# v7-flex2811_16x.net
KiCad netlist of a schematic drawn in EAGLE
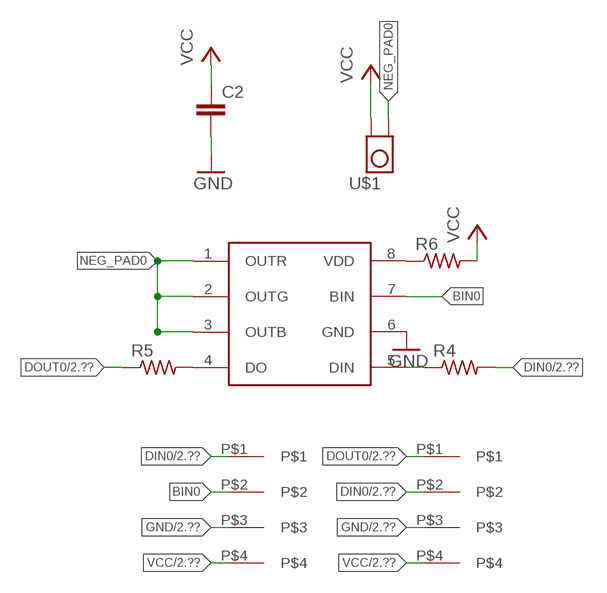
[diagram p0: schematic, sheet 1]
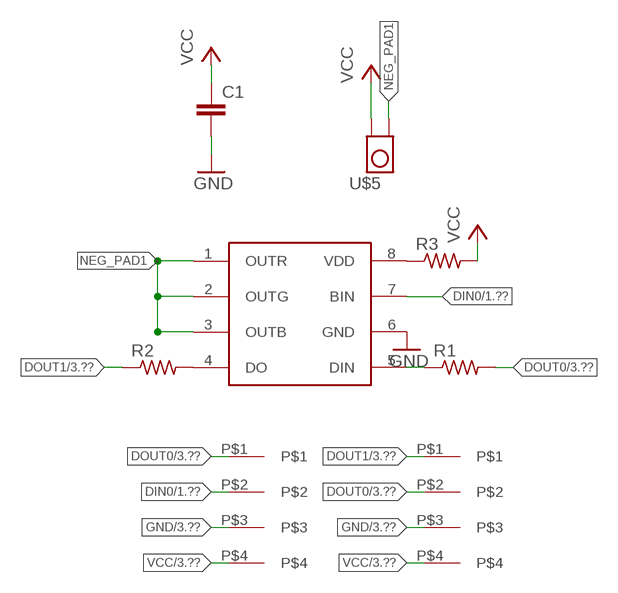
[diagram p1: schematic, sheet 2]
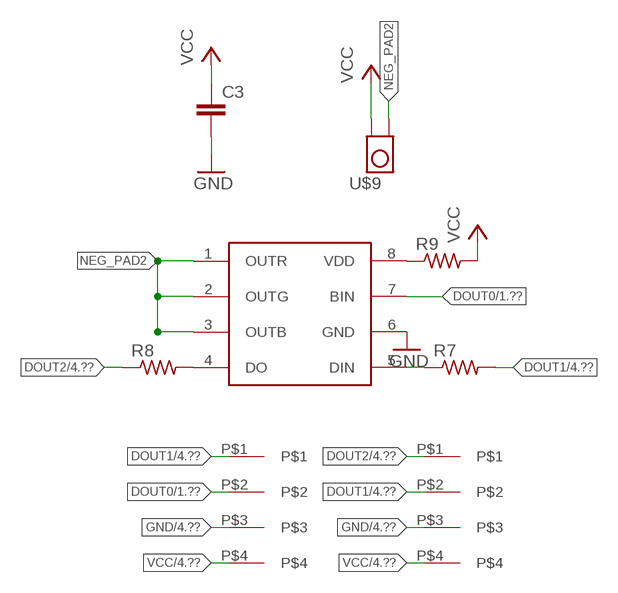
[diagram p2: schematic, sheet 3]
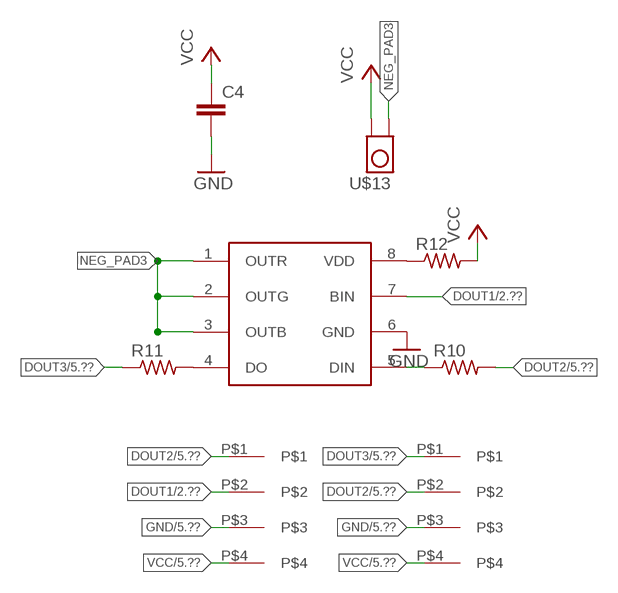
[diagram p3: schematic, sheet 4]
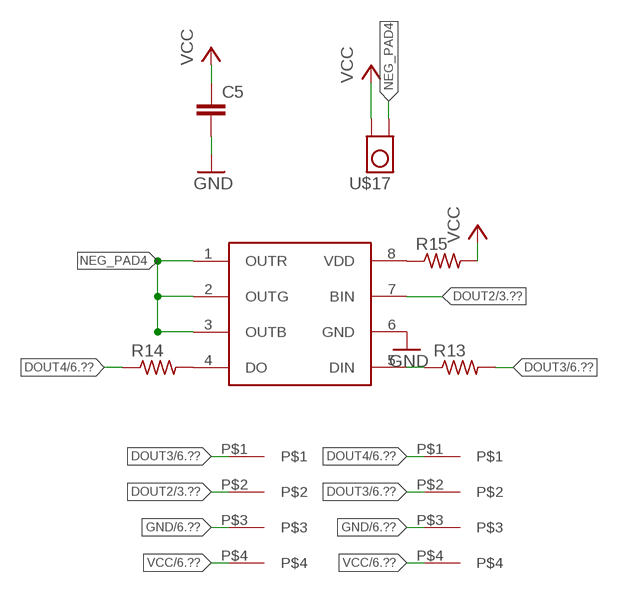
[diagram p4: schematic, sheet 5]
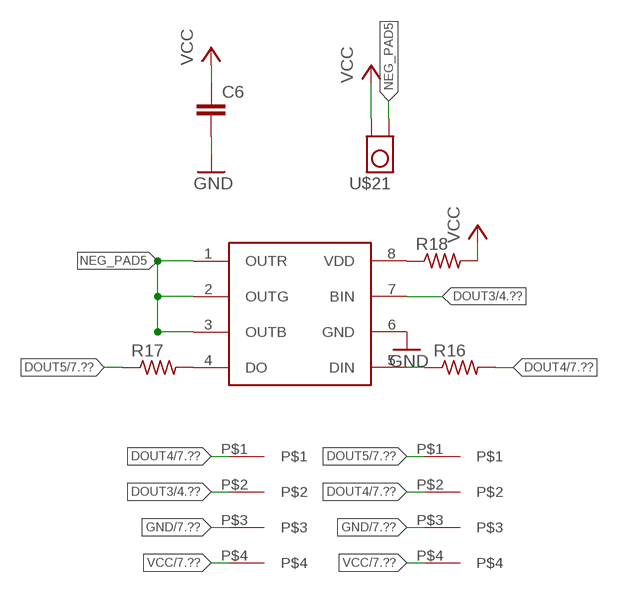
[diagram p5: schematic, sheet 6]
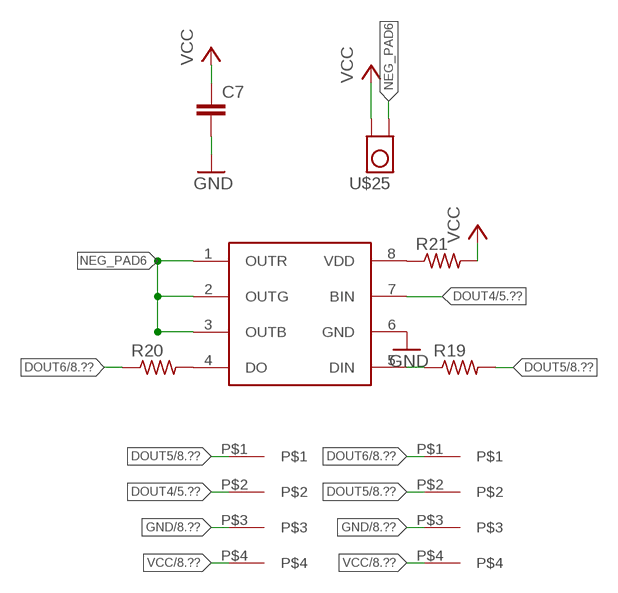
[diagram p6: schematic, sheet 7]
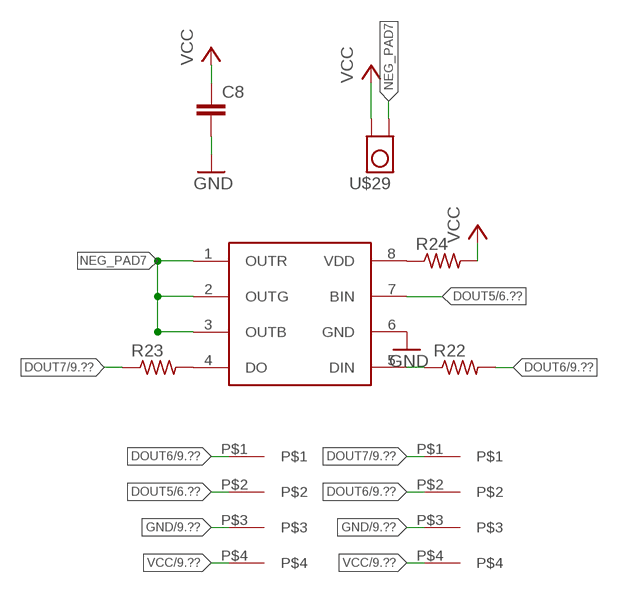
[diagram p7: schematic, sheet 8]
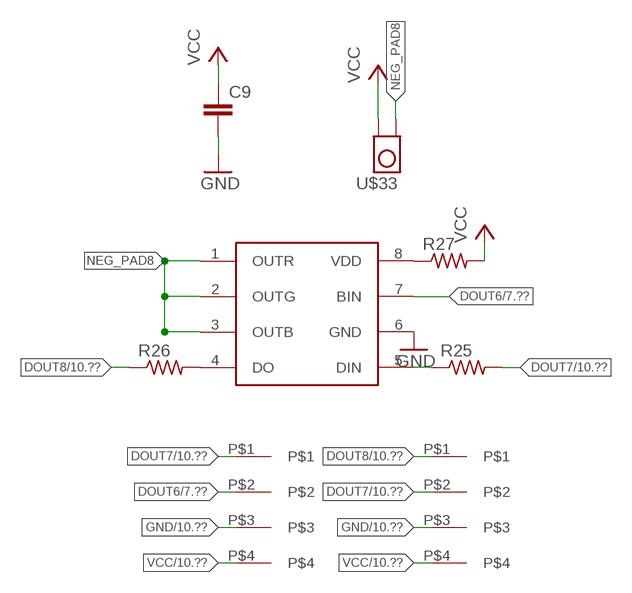
[diagram p8: schematic, sheet 9]
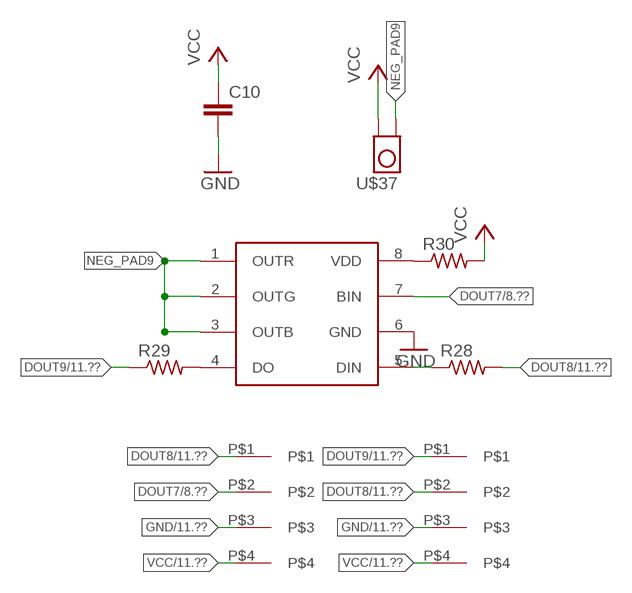
[diagram p9: schematic, sheet 10]
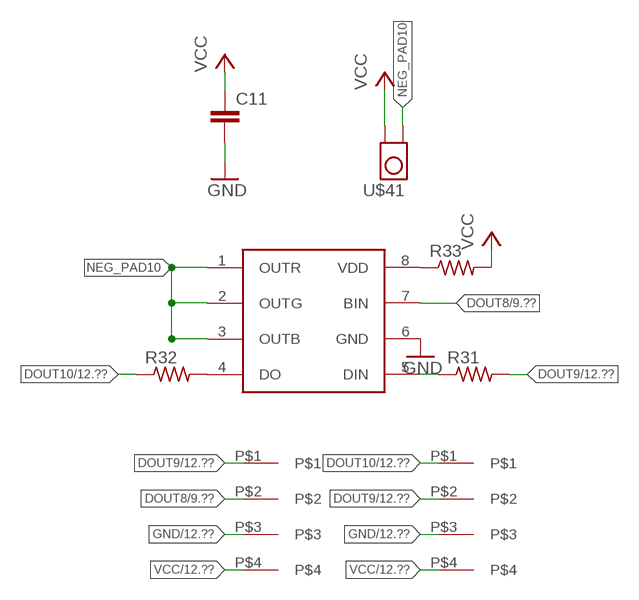
[diagram p10: schematic, sheet 11]
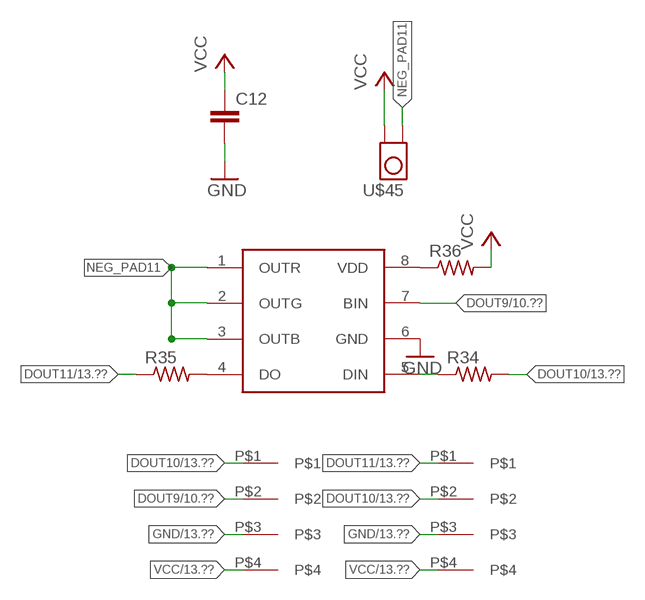
[diagram p11: schematic, sheet 12]
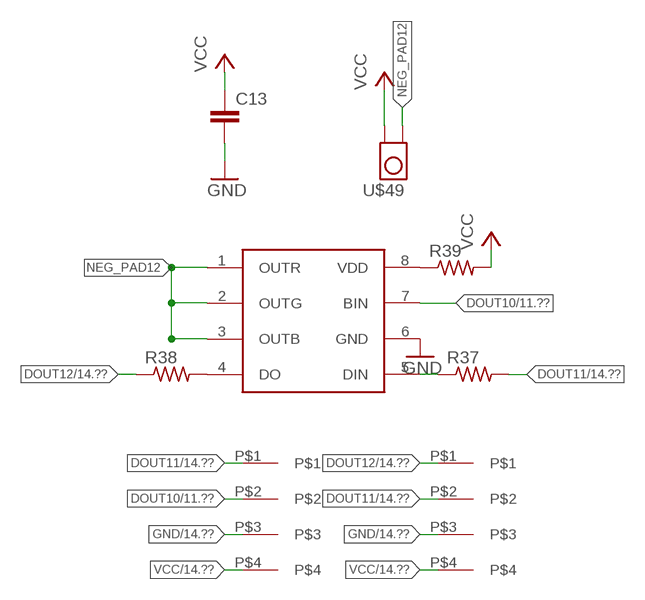
[diagram p12: schematic, sheet 13]
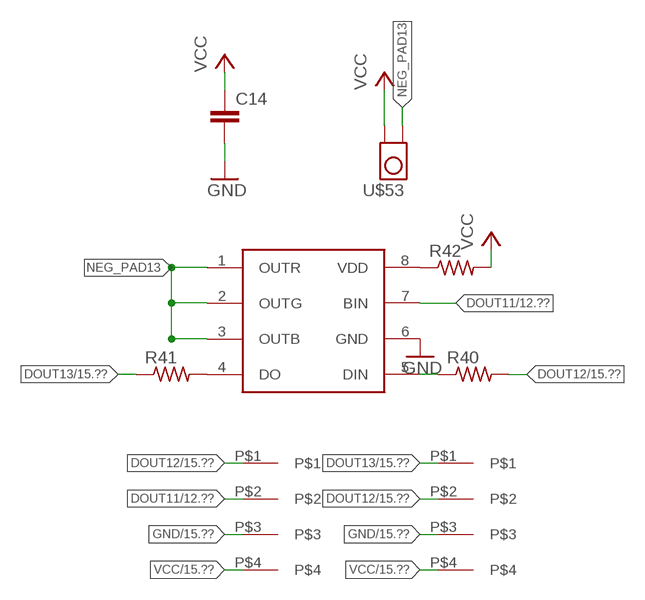
[diagram p13: schematic, sheet 14]
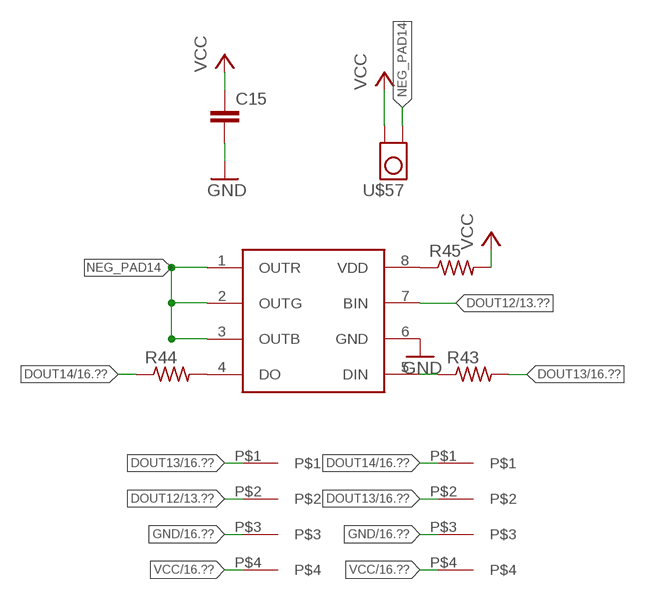
[diagram p14: schematic, sheet 15]
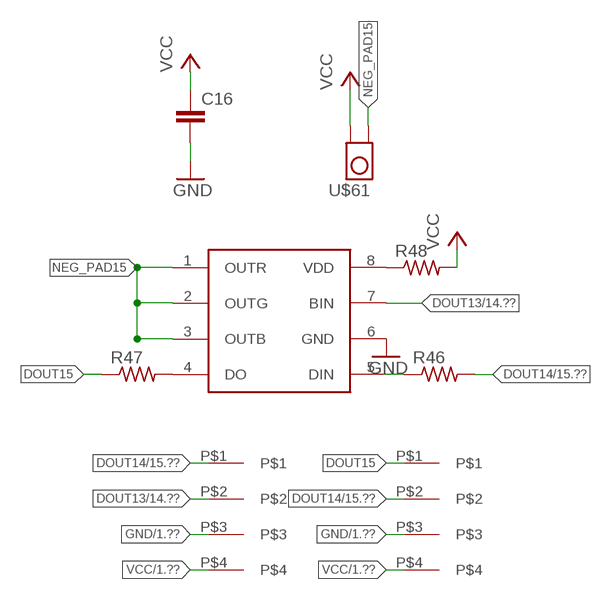
[diagram p15: schematic, sheet 16]

(export (version "E")
  (design (tool "Eeschema 10.0.6"))
  (components
    (comp (ref "C3")
      (value "C-EUC0201")
      (footprint "eagle-import:C0201")
      (libsource (lib "eagle-import") (part "C-EUC0201"))
    )
    (comp (ref "R7")
      (value "R-US_R0201")
      (footprint "eagle-import:R0201")
      (libsource (lib "eagle-import") (part "R-US_R0201"))
    )
    (comp (ref "R8")
      (value "R-US_R0201")
      (footprint "eagle-import:R0201")
      (libsource (lib "eagle-import") (part "R-US_R0201"))
    )
    (comp (ref "R9")
      (value "R-US_R0201")
      (footprint "eagle-import:R0201")
      (libsource (lib "eagle-import") (part "R-US_R0201"))
    )
    (comp (ref "U$9")
      (value "TP_4MM_MED_PAD")
      (footprint "eagle-import:TP_4MM_MED_PAD")
      (libsource (lib "eagle-import") (part "TP_4MM_MED_PAD"))
    )
    (comp (ref "U$10")
      (value "WS2818")
      (footprint "eagle-import:SO08")
      (libsource (lib "eagle-import") (part "WS2818"))
    )
    (comp (ref "U$11")
      (value "4PAD")
      (footprint "eagle-import:4PAD")
      (libsource (lib "eagle-import") (part "4PAD"))
    )
    (comp (ref "U$12")
      (value "4PAD")
      (footprint "eagle-import:4PAD")
      (libsource (lib "eagle-import") (part "4PAD"))
    )
    (comp (ref "C12")
      (value "C-EUC0201")
      (footprint "eagle-import:C0201")
      (libsource (lib "eagle-import") (part "C-EUC0201"))
    )
    (comp (ref "R34")
      (value "R-US_R0201")
      (footprint "eagle-import:R0201")
      (libsource (lib "eagle-import") (part "R-US_R0201"))
    )
    (comp (ref "R35")
      (value "R-US_R0201")
      (footprint "eagle-import:R0201")
      (libsource (lib "eagle-import") (part "R-US_R0201"))
    )
    (comp (ref "R36")
      (value "R-US_R0201")
      (footprint "eagle-import:R0201")
      (libsource (lib "eagle-import") (part "R-US_R0201"))
    )
    (comp (ref "U$45")
      (value "TP_4MM_MED_PAD")
      (footprint "eagle-import:TP_4MM_MED_PAD")
      (libsource (lib "eagle-import") (part "TP_4MM_MED_PAD"))
    )
    (comp (ref "U$46")
      (value "WS2818")
      (footprint "eagle-import:SO08")
      (libsource (lib "eagle-import") (part "WS2818"))
    )
    (comp (ref "U$47")
      (value "4PAD")
      (footprint "eagle-import:4PAD")
      (libsource (lib "eagle-import") (part "4PAD"))
    )
    (comp (ref "U$48")
      (value "4PAD")
      (footprint "eagle-import:4PAD")
      (libsource (lib "eagle-import") (part "4PAD"))
    )
    (comp (ref "C16")
      (value "C-EUC0201")
      (footprint "eagle-import:C0201")
      (libsource (lib "eagle-import") (part "C-EUC0201"))
    )
    (comp (ref "R46")
      (value "R-US_R0201")
      (footprint "eagle-import:R0201")
      (libsource (lib "eagle-import") (part "R-US_R0201"))
    )
    (comp (ref "R47")
      (value "R-US_R0201")
      (footprint "eagle-import:R0201")
      (libsource (lib "eagle-import") (part "R-US_R0201"))
    )
    (comp (ref "R48")
      (value "R-US_R0201")
      (footprint "eagle-import:R0201")
      (libsource (lib "eagle-import") (part "R-US_R0201"))
    )
    (comp (ref "U$61")
      (value "TP_4MM_MED_PAD")
      (footprint "eagle-import:TP_4MM_MED_PAD")
      (libsource (lib "eagle-import") (part "TP_4MM_MED_PAD"))
    )
    (comp (ref "U$62")
      (value "WS2818")
      (footprint "eagle-import:SO08")
      (libsource (lib "eagle-import") (part "WS2818"))
    )
    (comp (ref "U$63")
      (value "4PAD")
      (footprint "eagle-import:4PAD")
      (libsource (lib "eagle-import") (part "4PAD"))
    )
    (comp (ref "U$64")
      (value "4PAD")
      (footprint "eagle-import:4PAD")
      (libsource (lib "eagle-import") (part "4PAD"))
    )
    (comp (ref "C8")
      (value "C-EUC0201")
      (footprint "eagle-import:C0201")
      (libsource (lib "eagle-import") (part "C-EUC0201"))
    )
    (comp (ref "R22")
      (value "R-US_R0201")
      (footprint "eagle-import:R0201")
      (libsource (lib "eagle-import") (part "R-US_R0201"))
    )
    (comp (ref "R23")
      (value "R-US_R0201")
      (footprint "eagle-import:R0201")
      (libsource (lib "eagle-import") (part "R-US_R0201"))
    )
    (comp (ref "R24")
      (value "R-US_R0201")
      (footprint "eagle-import:R0201")
      (libsource (lib "eagle-import") (part "R-US_R0201"))
    )
    (comp (ref "U$29")
      (value "TP_4MM_MED_PAD")
      (footprint "eagle-import:TP_4MM_MED_PAD")
      (libsource (lib "eagle-import") (part "TP_4MM_MED_PAD"))
    )
    (comp (ref "U$30")
      (value "WS2818")
      (footprint "eagle-import:SO08")
      (libsource (lib "eagle-import") (part "WS2818"))
    )
    (comp (ref "U$31")
      (value "4PAD")
      (footprint "eagle-import:4PAD")
      (libsource (lib "eagle-import") (part "4PAD"))
    )
    (comp (ref "U$32")
      (value "4PAD")
      (footprint "eagle-import:4PAD")
      (libsource (lib "eagle-import") (part "4PAD"))
    )
    (comp (ref "C6")
      (value "C-EUC0201")
      (footprint "eagle-import:C0201")
      (libsource (lib "eagle-import") (part "C-EUC0201"))
    )
    (comp (ref "R16")
      (value "R-US_R0201")
      (footprint "eagle-import:R0201")
      (libsource (lib "eagle-import") (part "R-US_R0201"))
    )
    (comp (ref "R17")
      (value "R-US_R0201")
      (footprint "eagle-import:R0201")
      (libsource (lib "eagle-import") (part "R-US_R0201"))
    )
    (comp (ref "R18")
      (value "R-US_R0201")
      (footprint "eagle-import:R0201")
      (libsource (lib "eagle-import") (part "R-US_R0201"))
    )
    (comp (ref "U$21")
      (value "TP_4MM_MED_PAD")
      (footprint "eagle-import:TP_4MM_MED_PAD")
      (libsource (lib "eagle-import") (part "TP_4MM_MED_PAD"))
    )
    (comp (ref "U$22")
      (value "WS2818")
      (footprint "eagle-import:SO08")
      (libsource (lib "eagle-import") (part "WS2818"))
    )
    (comp (ref "U$23")
      (value "4PAD")
      (footprint "eagle-import:4PAD")
      (libsource (lib "eagle-import") (part "4PAD"))
    )
    (comp (ref "U$24")
      (value "4PAD")
      (footprint "eagle-import:4PAD")
      (libsource (lib "eagle-import") (part "4PAD"))
    )
    (comp (ref "C4")
      (value "C-EUC0201")
      (footprint "eagle-import:C0201")
      (libsource (lib "eagle-import") (part "C-EUC0201"))
    )
    (comp (ref "R10")
      (value "R-US_R0201")
      (footprint "eagle-import:R0201")
      (libsource (lib "eagle-import") (part "R-US_R0201"))
    )
    (comp (ref "R11")
      (value "R-US_R0201")
      (footprint "eagle-import:R0201")
      (libsource (lib "eagle-import") (part "R-US_R0201"))
    )
    (comp (ref "R12")
      (value "R-US_R0201")
      (footprint "eagle-import:R0201")
      (libsource (lib "eagle-import") (part "R-US_R0201"))
    )
    (comp (ref "U$13")
      (value "TP_4MM_MED_PAD")
      (footprint "eagle-import:TP_4MM_MED_PAD")
      (libsource (lib "eagle-import") (part "TP_4MM_MED_PAD"))
    )
    (comp (ref "U$14")
      (value "WS2818")
      (footprint "eagle-import:SO08")
      (libsource (lib "eagle-import") (part "WS2818"))
    )
    (comp (ref "U$15")
      (value "4PAD")
      (footprint "eagle-import:4PAD")
      (libsource (lib "eagle-import") (part "4PAD"))
    )
    (comp (ref "U$16")
      (value "4PAD")
      (footprint "eagle-import:4PAD")
      (libsource (lib "eagle-import") (part "4PAD"))
    )
    (comp (ref "C13")
      (value "C-EUC0201")
      (footprint "eagle-import:C0201")
      (libsource (lib "eagle-import") (part "C-EUC0201"))
    )
    (comp (ref "R37")
      (value "R-US_R0201")
      (footprint "eagle-import:R0201")
      (libsource (lib "eagle-import") (part "R-US_R0201"))
    )
    (comp (ref "R38")
      (value "R-US_R0201")
      (footprint "eagle-import:R0201")
      (libsource (lib "eagle-import") (part "R-US_R0201"))
    )
    (comp (ref "R39")
      (value "R-US_R0201")
      (footprint "eagle-import:R0201")
      (libsource (lib "eagle-import") (part "R-US_R0201"))
    )
    (comp (ref "U$49")
      (value "TP_4MM_MED_PAD")
      (footprint "eagle-import:TP_4MM_MED_PAD")
      (libsource (lib "eagle-import") (part "TP_4MM_MED_PAD"))
    )
    (comp (ref "U$50")
      (value "WS2818")
      (footprint "eagle-import:SO08")
      (libsource (lib "eagle-import") (part "WS2818"))
    )
    (comp (ref "U$51")
      (value "4PAD")
      (footprint "eagle-import:4PAD")
      (libsource (lib "eagle-import") (part "4PAD"))
    )
    (comp (ref "U$52")
      (value "4PAD")
      (footprint "eagle-import:4PAD")
      (libsource (lib "eagle-import") (part "4PAD"))
    )
    (comp (ref "C10")
      (value "C-EUC0201")
      (footprint "eagle-import:C0201")
      (libsource (lib "eagle-import") (part "C-EUC0201"))
    )
    (comp (ref "R28")
      (value "R-US_R0201")
      (footprint "eagle-import:R0201")
      (libsource (lib "eagle-import") (part "R-US_R0201"))
    )
    (comp (ref "R29")
      (value "R-US_R0201")
      (footprint "eagle-import:R0201")
      (libsource (lib "eagle-import") (part "R-US_R0201"))
    )
    (comp (ref "R30")
      (value "R-US_R0201")
      (footprint "eagle-import:R0201")
      (libsource (lib "eagle-import") (part "R-US_R0201"))
    )
    (comp (ref "U$37")
      (value "TP_4MM_MED_PAD")
      (footprint "eagle-import:TP_4MM_MED_PAD")
      (libsource (lib "eagle-import") (part "TP_4MM_MED_PAD"))
    )
    (comp (ref "U$38")
      (value "WS2818")
      (footprint "eagle-import:SO08")
      (libsource (lib "eagle-import") (part "WS2818"))
    )
    (comp (ref "U$39")
      (value "4PAD")
      (footprint "eagle-import:4PAD")
      (libsource (lib "eagle-import") (part "4PAD"))
    )
    (comp (ref "U$40")
      (value "4PAD")
      (footprint "eagle-import:4PAD")
      (libsource (lib "eagle-import") (part "4PAD"))
    )
    (comp (ref "C14")
      (value "C-EUC0201")
      (footprint "eagle-import:C0201")
      (libsource (lib "eagle-import") (part "C-EUC0201"))
    )
    (comp (ref "R40")
      (value "R-US_R0201")
      (footprint "eagle-import:R0201")
      (libsource (lib "eagle-import") (part "R-US_R0201"))
    )
    (comp (ref "R41")
      (value "R-US_R0201")
      (footprint "eagle-import:R0201")
      (libsource (lib "eagle-import") (part "R-US_R0201"))
    )
    (comp (ref "R42")
      (value "R-US_R0201")
      (footprint "eagle-import:R0201")
      (libsource (lib "eagle-import") (part "R-US_R0201"))
    )
    (comp (ref "U$53")
      (value "TP_4MM_MED_PAD")
      (footprint "eagle-import:TP_4MM_MED_PAD")
      (libsource (lib "eagle-import") (part "TP_4MM_MED_PAD"))
    )
    (comp (ref "U$54")
      (value "WS2818")
      (footprint "eagle-import:SO08")
      (libsource (lib "eagle-import") (part "WS2818"))
    )
    (comp (ref "U$55")
      (value "4PAD")
      (footprint "eagle-import:4PAD")
      (libsource (lib "eagle-import") (part "4PAD"))
    )
    (comp (ref "U$56")
      (value "4PAD")
      (footprint "eagle-import:4PAD")
      (libsource (lib "eagle-import") (part "4PAD"))
    )
    (comp (ref "C7")
      (value "C-EUC0201")
      (footprint "eagle-import:C0201")
      (libsource (lib "eagle-import") (part "C-EUC0201"))
    )
    (comp (ref "R19")
      (value "R-US_R0201")
      (footprint "eagle-import:R0201")
      (libsource (lib "eagle-import") (part "R-US_R0201"))
    )
    (comp (ref "R20")
      (value "R-US_R0201")
      (footprint "eagle-import:R0201")
      (libsource (lib "eagle-import") (part "R-US_R0201"))
    )
    (comp (ref "R21")
      (value "R-US_R0201")
      (footprint "eagle-import:R0201")
      (libsource (lib "eagle-import") (part "R-US_R0201"))
    )
    (comp (ref "U$25")
      (value "TP_4MM_MED_PAD")
      (footprint "eagle-import:TP_4MM_MED_PAD")
      (libsource (lib "eagle-import") (part "TP_4MM_MED_PAD"))
    )
    (comp (ref "U$26")
      (value "WS2818")
      (footprint "eagle-import:SO08")
      (libsource (lib "eagle-import") (part "WS2818"))
    )
    (comp (ref "U$27")
      (value "4PAD")
      (footprint "eagle-import:4PAD")
      (libsource (lib "eagle-import") (part "4PAD"))
    )
    (comp (ref "U$28")
      (value "4PAD")
      (footprint "eagle-import:4PAD")
      (libsource (lib "eagle-import") (part "4PAD"))
    )
    (comp (ref "C11")
      (value "C-EUC0201")
      (footprint "eagle-import:C0201")
      (libsource (lib "eagle-import") (part "C-EUC0201"))
    )
    (comp (ref "R31")
      (value "R-US_R0201")
      (footprint "eagle-import:R0201")
      (libsource (lib "eagle-import") (part "R-US_R0201"))
    )
    (comp (ref "R32")
      (value "R-US_R0201")
      (footprint "eagle-import:R0201")
      (libsource (lib "eagle-import") (part "R-US_R0201"))
    )
    (comp (ref "R33")
      (value "R-US_R0201")
      (footprint "eagle-import:R0201")
      (libsource (lib "eagle-import") (part "R-US_R0201"))
    )
    (comp (ref "U$41")
      (value "TP_4MM_MED_PAD")
      (footprint "eagle-import:TP_4MM_MED_PAD")
      (libsource (lib "eagle-import") (part "TP_4MM_MED_PAD"))
    )
    (comp (ref "U$42")
      (value "WS2818")
      (footprint "eagle-import:SO08")
      (libsource (lib "eagle-import") (part "WS2818"))
    )
    (comp (ref "U$43")
      (value "4PAD")
      (footprint "eagle-import:4PAD")
      (libsource (lib "eagle-import") (part "4PAD"))
    )
    (comp (ref "U$44")
      (value "4PAD")
      (footprint "eagle-import:4PAD")
      (libsource (lib "eagle-import") (part "4PAD"))
    )
    (comp (ref "C15")
      (value "C-EUC0201")
      (footprint "eagle-import:C0201")
      (libsource (lib "eagle-import") (part "C-EUC0201"))
    )
    (comp (ref "R43")
      (value "R-US_R0201")
      (footprint "eagle-import:R0201")
      (libsource (lib "eagle-import") (part "R-US_R0201"))
    )
    (comp (ref "R44")
      (value "R-US_R0201")
      (footprint "eagle-import:R0201")
      (libsource (lib "eagle-import") (part "R-US_R0201"))
    )
    (comp (ref "R45")
      (value "R-US_R0201")
      (footprint "eagle-import:R0201")
      (libsource (lib "eagle-import") (part "R-US_R0201"))
    )
    (comp (ref "U$57")
      (value "TP_4MM_MED_PAD")
      (footprint "eagle-import:TP_4MM_MED_PAD")
      (libsource (lib "eagle-import") (part "TP_4MM_MED_PAD"))
    )
    (comp (ref "U$58")
      (value "WS2818")
      (footprint "eagle-import:SO08")
      (libsource (lib "eagle-import") (part "WS2818"))
    )
    (comp (ref "U$59")
      (value "4PAD")
      (footprint "eagle-import:4PAD")
      (libsource (lib "eagle-import") (part "4PAD"))
    )
    (comp (ref "U$60")
      (value "4PAD")
      (footprint "eagle-import:4PAD")
      (libsource (lib "eagle-import") (part "4PAD"))
    )
    (comp (ref "C2")
      (value "C-EUC0201")
      (footprint "eagle-import:C0201")
      (libsource (lib "eagle-import") (part "C-EUC0201"))
    )
    (comp (ref "R4")
      (value "R-US_R0201")
      (footprint "eagle-import:R0201")
      (libsource (lib "eagle-import") (part "R-US_R0201"))
    )
    (comp (ref "R5")
      (value "R-US_R0201")
      (footprint "eagle-import:R0201")
      (libsource (lib "eagle-import") (part "R-US_R0201"))
    )
    (comp (ref "R6")
      (value "R-US_R0201")
      (footprint "eagle-import:R0201")
      (libsource (lib "eagle-import") (part "R-US_R0201"))
    )
    (comp (ref "U$1")
      (value "TP_4MM_MED_PAD")
      (footprint "eagle-import:TP_4MM_MED_PAD")
      (libsource (lib "eagle-import") (part "TP_4MM_MED_PAD"))
    )
    (comp (ref "U$2")
      (value "WS2818")
      (footprint "eagle-import:SO08")
      (libsource (lib "eagle-import") (part "WS2818"))
    )
    (comp (ref "U$3")
      (value "4PAD")
      (footprint "eagle-import:4PAD")
      (libsource (lib "eagle-import") (part "4PAD"))
    )
    (comp (ref "U$4")
      (value "4PAD")
      (footprint "eagle-import:4PAD")
      (libsource (lib "eagle-import") (part "4PAD"))
    )
    (comp (ref "C9")
      (value "C-EUC0201")
      (footprint "eagle-import:C0201")
      (libsource (lib "eagle-import") (part "C-EUC0201"))
    )
    (comp (ref "R25")
      (value "R-US_R0201")
      (footprint "eagle-import:R0201")
      (libsource (lib "eagle-import") (part "R-US_R0201"))
    )
    (comp (ref "R26")
      (value "R-US_R0201")
      (footprint "eagle-import:R0201")
      (libsource (lib "eagle-import") (part "R-US_R0201"))
    )
    (comp (ref "R27")
      (value "R-US_R0201")
      (footprint "eagle-import:R0201")
      (libsource (lib "eagle-import") (part "R-US_R0201"))
    )
    (comp (ref "U$33")
      (value "TP_4MM_MED_PAD")
      (footprint "eagle-import:TP_4MM_MED_PAD")
      (libsource (lib "eagle-import") (part "TP_4MM_MED_PAD"))
    )
    (comp (ref "U$34")
      (value "WS2818")
      (footprint "eagle-import:SO08")
      (libsource (lib "eagle-import") (part "WS2818"))
    )
    (comp (ref "U$35")
      (value "4PAD")
      (footprint "eagle-import:4PAD")
      (libsource (lib "eagle-import") (part "4PAD"))
    )
    (comp (ref "U$36")
      (value "4PAD")
      (footprint "eagle-import:4PAD")
      (libsource (lib "eagle-import") (part "4PAD"))
    )
    (comp (ref "C1")
      (value "C-EUC0201")
      (footprint "eagle-import:C0201")
      (libsource (lib "eagle-import") (part "C-EUC0201"))
    )
    (comp (ref "R1")
      (value "R-US_R0201")
      (footprint "eagle-import:R0201")
      (libsource (lib "eagle-import") (part "R-US_R0201"))
    )
    (comp (ref "R2")
      (value "R-US_R0201")
      (footprint "eagle-import:R0201")
      (libsource (lib "eagle-import") (part "R-US_R0201"))
    )
    (comp (ref "R3")
      (value "R-US_R0201")
      (footprint "eagle-import:R0201")
      (libsource (lib "eagle-import") (part "R-US_R0201"))
    )
    (comp (ref "U$5")
      (value "TP_4MM_MED_PAD")
      (footprint "eagle-import:TP_4MM_MED_PAD")
      (libsource (lib "eagle-import") (part "TP_4MM_MED_PAD"))
    )
    (comp (ref "U$6")
      (value "WS2818")
      (footprint "eagle-import:SO08")
      (libsource (lib "eagle-import") (part "WS2818"))
    )
    (comp (ref "U$7")
      (value "4PAD")
      (footprint "eagle-import:4PAD")
      (libsource (lib "eagle-import") (part "4PAD"))
    )
    (comp (ref "U$8")
      (value "4PAD")
      (footprint "eagle-import:4PAD")
      (libsource (lib "eagle-import") (part "4PAD"))
    )
    (comp (ref "C5")
      (value "C-EUC0201")
      (footprint "eagle-import:C0201")
      (libsource (lib "eagle-import") (part "C-EUC0201"))
    )
    (comp (ref "R13")
      (value "R-US_R0201")
      (footprint "eagle-import:R0201")
      (libsource (lib "eagle-import") (part "R-US_R0201"))
    )
    (comp (ref "R14")
      (value "R-US_R0201")
      (footprint "eagle-import:R0201")
      (libsource (lib "eagle-import") (part "R-US_R0201"))
    )
    (comp (ref "R15")
      (value "R-US_R0201")
      (footprint "eagle-import:R0201")
      (libsource (lib "eagle-import") (part "R-US_R0201"))
    )
    (comp (ref "U$17")
      (value "TP_4MM_MED_PAD")
      (footprint "eagle-import:TP_4MM_MED_PAD")
      (libsource (lib "eagle-import") (part "TP_4MM_MED_PAD"))
    )
    (comp (ref "U$18")
      (value "WS2818")
      (footprint "eagle-import:SO08")
      (libsource (lib "eagle-import") (part "WS2818"))
    )
    (comp (ref "U$19")
      (value "4PAD")
      (footprint "eagle-import:4PAD")
      (libsource (lib "eagle-import") (part "4PAD"))
    )
    (comp (ref "U$20")
      (value "4PAD")
      (footprint "eagle-import:4PAD")
      (libsource (lib "eagle-import") (part "4PAD"))
    )
  )
  (nets
    (net (code "1") (name "BIN0") (class "Default")
      (node (ref "U$2") (pin "7") (pinfunction "BIN_7") (pintype "bidirectional"))
      (node (ref "U$3") (pin "P$2") (pinfunction "P$2_P$2") (pintype "bidirectional"))
    )
    (net (code "2") (name "DIN0") (class "Default")
      (node (ref "R4") (pin "2") (pinfunction "2_2") (pintype "passive"))
      (node (ref "U$3") (pin "P$1") (pinfunction "P$1_P$1") (pintype "bidirectional"))
      (node (ref "U$4") (pin "P$2") (pinfunction "P$2_P$2") (pintype "bidirectional"))
      (node (ref "U$6") (pin "7") (pinfunction "BIN_7") (pintype "bidirectional"))
      (node (ref "U$7") (pin "P$2") (pinfunction "P$2_P$2") (pintype "bidirectional"))
    )
    (net (code "3") (name "DOUT0") (class "Default")
      (node (ref "R1") (pin "2") (pinfunction "2_2") (pintype "passive"))
      (node (ref "R5") (pin "1") (pinfunction "1_1") (pintype "passive"))
      (node (ref "U$10") (pin "7") (pinfunction "BIN_7") (pintype "bidirectional"))
      (node (ref "U$11") (pin "P$2") (pinfunction "P$2_P$2") (pintype "bidirectional"))
      (node (ref "U$4") (pin "P$1") (pinfunction "P$1_P$1") (pintype "bidirectional"))
      (node (ref "U$7") (pin "P$1") (pinfunction "P$1_P$1") (pintype "bidirectional"))
      (node (ref "U$8") (pin "P$2") (pinfunction "P$2_P$2") (pintype "bidirectional"))
    )
    (net (code "4") (name "DOUT1") (class "Default")
      (node (ref "R2") (pin "1") (pinfunction "1_1") (pintype "passive"))
      (node (ref "R7") (pin "2") (pinfunction "2_2") (pintype "passive"))
      (node (ref "U$11") (pin "P$1") (pinfunction "P$1_P$1") (pintype "bidirectional"))
      (node (ref "U$12") (pin "P$2") (pinfunction "P$2_P$2") (pintype "bidirectional"))
      (node (ref "U$14") (pin "7") (pinfunction "BIN_7") (pintype "bidirectional"))
      (node (ref "U$15") (pin "P$2") (pinfunction "P$2_P$2") (pintype "bidirectional"))
      (node (ref "U$8") (pin "P$1") (pinfunction "P$1_P$1") (pintype "bidirectional"))
    )
    (net (code "5") (name "DOUT2") (class "Default")
      (node (ref "R10") (pin "2") (pinfunction "2_2") (pintype "passive"))
      (node (ref "R8") (pin "1") (pinfunction "1_1") (pintype "passive"))
      (node (ref "U$12") (pin "P$1") (pinfunction "P$1_P$1") (pintype "bidirectional"))
      (node (ref "U$15") (pin "P$1") (pinfunction "P$1_P$1") (pintype "bidirectional"))
      (node (ref "U$16") (pin "P$2") (pinfunction "P$2_P$2") (pintype "bidirectional"))
      (node (ref "U$18") (pin "7") (pinfunction "BIN_7") (pintype "bidirectional"))
      (node (ref "U$19") (pin "P$2") (pinfunction "P$2_P$2") (pintype "bidirectional"))
    )
    (net (code "6") (name "DOUT3") (class "Default")
      (node (ref "R11") (pin "1") (pinfunction "1_1") (pintype "passive"))
      (node (ref "R13") (pin "2") (pinfunction "2_2") (pintype "passive"))
      (node (ref "U$16") (pin "P$1") (pinfunction "P$1_P$1") (pintype "bidirectional"))
      (node (ref "U$19") (pin "P$1") (pinfunction "P$1_P$1") (pintype "bidirectional"))
      (node (ref "U$20") (pin "P$2") (pinfunction "P$2_P$2") (pintype "bidirectional"))
      (node (ref "U$22") (pin "7") (pinfunction "BIN_7") (pintype "bidirectional"))
      (node (ref "U$23") (pin "P$2") (pinfunction "P$2_P$2") (pintype "bidirectional"))
    )
    (net (code "7") (name "DOUT4") (class "Default")
      (node (ref "R14") (pin "1") (pinfunction "1_1") (pintype "passive"))
      (node (ref "R16") (pin "2") (pinfunction "2_2") (pintype "passive"))
      (node (ref "U$20") (pin "P$1") (pinfunction "P$1_P$1") (pintype "bidirectional"))
      (node (ref "U$23") (pin "P$1") (pinfunction "P$1_P$1") (pintype "bidirectional"))
      (node (ref "U$24") (pin "P$2") (pinfunction "P$2_P$2") (pintype "bidirectional"))
      (node (ref "U$26") (pin "7") (pinfunction "BIN_7") (pintype "bidirectional"))
      (node (ref "U$27") (pin "P$2") (pinfunction "P$2_P$2") (pintype "bidirectional"))
    )
    (net (code "8") (name "DOUT5") (class "Default")
      (node (ref "R17") (pin "1") (pinfunction "1_1") (pintype "passive"))
      (node (ref "R19") (pin "2") (pinfunction "2_2") (pintype "passive"))
      (node (ref "U$24") (pin "P$1") (pinfunction "P$1_P$1") (pintype "bidirectional"))
      (node (ref "U$27") (pin "P$1") (pinfunction "P$1_P$1") (pintype "bidirectional"))
      (node (ref "U$28") (pin "P$2") (pinfunction "P$2_P$2") (pintype "bidirectional"))
      (node (ref "U$30") (pin "7") (pinfunction "BIN_7") (pintype "bidirectional"))
      (node (ref "U$31") (pin "P$2") (pinfunction "P$2_P$2") (pintype "bidirectional"))
    )
    (net (code "9") (name "DOUT6") (class "Default")
      (node (ref "R20") (pin "1") (pinfunction "1_1") (pintype "passive"))
      (node (ref "R22") (pin "2") (pinfunction "2_2") (pintype "passive"))
      (node (ref "U$28") (pin "P$1") (pinfunction "P$1_P$1") (pintype "bidirectional"))
      (node (ref "U$31") (pin "P$1") (pinfunction "P$1_P$1") (pintype "bidirectional"))
      (node (ref "U$32") (pin "P$2") (pinfunction "P$2_P$2") (pintype "bidirectional"))
      (node (ref "U$34") (pin "7") (pinfunction "BIN_7") (pintype "bidirectional"))
      (node (ref "U$35") (pin "P$2") (pinfunction "P$2_P$2") (pintype "bidirectional"))
    )
    (net (code "10") (name "DOUT7") (class "Default")
      (node (ref "R23") (pin "1") (pinfunction "1_1") (pintype "passive"))
      (node (ref "R25") (pin "2") (pinfunction "2_2") (pintype "passive"))
      (node (ref "U$32") (pin "P$1") (pinfunction "P$1_P$1") (pintype "bidirectional"))
      (node (ref "U$35") (pin "P$1") (pinfunction "P$1_P$1") (pintype "bidirectional"))
      (node (ref "U$36") (pin "P$2") (pinfunction "P$2_P$2") (pintype "bidirectional"))
      (node (ref "U$38") (pin "7") (pinfunction "BIN_7") (pintype "bidirectional"))
      (node (ref "U$39") (pin "P$2") (pinfunction "P$2_P$2") (pintype "bidirectional"))
    )
    (net (code "11") (name "DOUT8") (class "Default")
      (node (ref "R26") (pin "1") (pinfunction "1_1") (pintype "passive"))
      (node (ref "R28") (pin "2") (pinfunction "2_2") (pintype "passive"))
      (node (ref "U$36") (pin "P$1") (pinfunction "P$1_P$1") (pintype "bidirectional"))
      (node (ref "U$39") (pin "P$1") (pinfunction "P$1_P$1") (pintype "bidirectional"))
      (node (ref "U$40") (pin "P$2") (pinfunction "P$2_P$2") (pintype "bidirectional"))
      (node (ref "U$42") (pin "7") (pinfunction "BIN_7") (pintype "bidirectional"))
      (node (ref "U$43") (pin "P$2") (pinfunction "P$2_P$2") (pintype "bidirectional"))
    )
    (net (code "12") (name "DOUT9") (class "Default")
      (node (ref "R29") (pin "1") (pinfunction "1_1") (pintype "passive"))
      (node (ref "R31") (pin "2") (pinfunction "2_2") (pintype "passive"))
      (node (ref "U$40") (pin "P$1") (pinfunction "P$1_P$1") (pintype "bidirectional"))
      (node (ref "U$43") (pin "P$1") (pinfunction "P$1_P$1") (pintype "bidirectional"))
      (node (ref "U$44") (pin "P$2") (pinfunction "P$2_P$2") (pintype "bidirectional"))
      (node (ref "U$46") (pin "7") (pinfunction "BIN_7") (pintype "bidirectional"))
      (node (ref "U$47") (pin "P$2") (pinfunction "P$2_P$2") (pintype "bidirectional"))
    )
    (net (code "13") (name "DOUT10") (class "Default")
      (node (ref "R32") (pin "1") (pinfunction "1_1") (pintype "passive"))
      (node (ref "R34") (pin "2") (pinfunction "2_2") (pintype "passive"))
      (node (ref "U$44") (pin "P$1") (pinfunction "P$1_P$1") (pintype "bidirectional"))
      (node (ref "U$47") (pin "P$1") (pinfunction "P$1_P$1") (pintype "bidirectional"))
      (node (ref "U$48") (pin "P$2") (pinfunction "P$2_P$2") (pintype "bidirectional"))
      (node (ref "U$50") (pin "7") (pinfunction "BIN_7") (pintype "bidirectional"))
      (node (ref "U$51") (pin "P$2") (pinfunction "P$2_P$2") (pintype "bidirectional"))
    )
    (net (code "14") (name "DOUT11") (class "Default")
      (node (ref "R35") (pin "1") (pinfunction "1_1") (pintype "passive"))
      (node (ref "R37") (pin "2") (pinfunction "2_2") (pintype "passive"))
      (node (ref "U$48") (pin "P$1") (pinfunction "P$1_P$1") (pintype "bidirectional"))
      (node (ref "U$51") (pin "P$1") (pinfunction "P$1_P$1") (pintype "bidirectional"))
      (node (ref "U$52") (pin "P$2") (pinfunction "P$2_P$2") (pintype "bidirectional"))
      (node (ref "U$54") (pin "7") (pinfunction "BIN_7") (pintype "bidirectional"))
      (node (ref "U$55") (pin "P$2") (pinfunction "P$2_P$2") (pintype "bidirectional"))
    )
    (net (code "15") (name "DOUT12") (class "Default")
      (node (ref "R38") (pin "1") (pinfunction "1_1") (pintype "passive"))
      (node (ref "R40") (pin "2") (pinfunction "2_2") (pintype "passive"))
      (node (ref "U$52") (pin "P$1") (pinfunction "P$1_P$1") (pintype "bidirectional"))
      (node (ref "U$55") (pin "P$1") (pinfunction "P$1_P$1") (pintype "bidirectional"))
      (node (ref "U$56") (pin "P$2") (pinfunction "P$2_P$2") (pintype "bidirectional"))
      (node (ref "U$58") (pin "7") (pinfunction "BIN_7") (pintype "bidirectional"))
      (node (ref "U$59") (pin "P$2") (pinfunction "P$2_P$2") (pintype "bidirectional"))
    )
    (net (code "16") (name "DOUT13") (class "Default")
      (node (ref "R41") (pin "1") (pinfunction "1_1") (pintype "passive"))
      (node (ref "R43") (pin "2") (pinfunction "2_2") (pintype "passive"))
      (node (ref "U$56") (pin "P$1") (pinfunction "P$1_P$1") (pintype "bidirectional"))
      (node (ref "U$59") (pin "P$1") (pinfunction "P$1_P$1") (pintype "bidirectional"))
      (node (ref "U$60") (pin "P$2") (pinfunction "P$2_P$2") (pintype "bidirectional"))
      (node (ref "U$62") (pin "7") (pinfunction "BIN_7") (pintype "bidirectional"))
      (node (ref "U$63") (pin "P$2") (pinfunction "P$2_P$2") (pintype "bidirectional"))
    )
    (net (code "17") (name "DOUT14") (class "Default")
      (node (ref "R44") (pin "1") (pinfunction "1_1") (pintype "passive"))
      (node (ref "R46") (pin "2") (pinfunction "2_2") (pintype "passive"))
      (node (ref "U$60") (pin "P$1") (pinfunction "P$1_P$1") (pintype "bidirectional"))
      (node (ref "U$63") (pin "P$1") (pinfunction "P$1_P$1") (pintype "bidirectional"))
      (node (ref "U$64") (pin "P$2") (pinfunction "P$2_P$2") (pintype "bidirectional"))
    )
    (net (code "18") (name "DOUT15") (class "Default")
      (node (ref "R47") (pin "1") (pinfunction "1_1") (pintype "passive"))
      (node (ref "U$64") (pin "P$1") (pinfunction "P$1_P$1") (pintype "bidirectional"))
    )
    (net (code "19") (name "GND") (class "Default")
      (node (ref "C1") (pin "2") (pinfunction "2_2") (pintype "passive"))
      (node (ref "C10") (pin "2") (pinfunction "2_2") (pintype "passive"))
      (node (ref "C11") (pin "2") (pinfunction "2_2") (pintype "passive"))
      (node (ref "C12") (pin "2") (pinfunction "2_2") (pintype "passive"))
      (node (ref "C13") (pin "2") (pinfunction "2_2") (pintype "passive"))
      (node (ref "C14") (pin "2") (pinfunction "2_2") (pintype "passive"))
      (node (ref "C15") (pin "2") (pinfunction "2_2") (pintype "passive"))
      (node (ref "C16") (pin "2") (pinfunction "2_2") (pintype "passive"))
      (node (ref "C2") (pin "2") (pinfunction "2_2") (pintype "passive"))
      (node (ref "C3") (pin "2") (pinfunction "2_2") (pintype "passive"))
      (node (ref "C4") (pin "2") (pinfunction "2_2") (pintype "passive"))
      (node (ref "C5") (pin "2") (pinfunction "2_2") (pintype "passive"))
      (node (ref "C6") (pin "2") (pinfunction "2_2") (pintype "passive"))
      (node (ref "C7") (pin "2") (pinfunction "2_2") (pintype "passive"))
      (node (ref "C8") (pin "2") (pinfunction "2_2") (pintype "passive"))
      (node (ref "C9") (pin "2") (pinfunction "2_2") (pintype "passive"))
      (node (ref "U$10") (pin "6") (pinfunction "GND_6") (pintype "bidirectional"))
      (node (ref "U$11") (pin "P$3") (pinfunction "P$3_P$3") (pintype "bidirectional"))
      (node (ref "U$12") (pin "P$3") (pinfunction "P$3_P$3") (pintype "bidirectional"))
      (node (ref "U$14") (pin "6") (pinfunction "GND_6") (pintype "bidirectional"))
      (node (ref "U$15") (pin "P$3") (pinfunction "P$3_P$3") (pintype "bidirectional"))
      (node (ref "U$16") (pin "P$3") (pinfunction "P$3_P$3") (pintype "bidirectional"))
      (node (ref "U$18") (pin "6") (pinfunction "GND_6") (pintype "bidirectional"))
      (node (ref "U$19") (pin "P$3") (pinfunction "P$3_P$3") (pintype "bidirectional"))
      (node (ref "U$2") (pin "6") (pinfunction "GND_6") (pintype "bidirectional"))
      (node (ref "U$20") (pin "P$3") (pinfunction "P$3_P$3") (pintype "bidirectional"))
      (node (ref "U$22") (pin "6") (pinfunction "GND_6") (pintype "bidirectional"))
      (node (ref "U$23") (pin "P$3") (pinfunction "P$3_P$3") (pintype "bidirectional"))
      (node (ref "U$24") (pin "P$3") (pinfunction "P$3_P$3") (pintype "bidirectional"))
      (node (ref "U$26") (pin "6") (pinfunction "GND_6") (pintype "bidirectional"))
      (node (ref "U$27") (pin "P$3") (pinfunction "P$3_P$3") (pintype "bidirectional"))
      (node (ref "U$28") (pin "P$3") (pinfunction "P$3_P$3") (pintype "bidirectional"))
      (node (ref "U$3") (pin "P$3") (pinfunction "P$3_P$3") (pintype "bidirectional"))
      (node (ref "U$30") (pin "6") (pinfunction "GND_6") (pintype "bidirectional"))
      (node (ref "U$31") (pin "P$3") (pinfunction "P$3_P$3") (pintype "bidirectional"))
      (node (ref "U$32") (pin "P$3") (pinfunction "P$3_P$3") (pintype "bidirectional"))
      (node (ref "U$34") (pin "6") (pinfunction "GND_6") (pintype "bidirectional"))
      (node (ref "U$35") (pin "P$3") (pinfunction "P$3_P$3") (pintype "bidirectional"))
      (node (ref "U$36") (pin "P$3") (pinfunction "P$3_P$3") (pintype "bidirectional"))
      (node (ref "U$38") (pin "6") (pinfunction "GND_6") (pintype "bidirectional"))
      (node (ref "U$39") (pin "P$3") (pinfunction "P$3_P$3") (pintype "bidirectional"))
      (node (ref "U$4") (pin "P$3") (pinfunction "P$3_P$3") (pintype "bidirectional"))
      (node (ref "U$40") (pin "P$3") (pinfunction "P$3_P$3") (pintype "bidirectional"))
      (node (ref "U$42") (pin "6") (pinfunction "GND_6") (pintype "bidirectional"))
      (node (ref "U$43") (pin "P$3") (pinfunction "P$3_P$3") (pintype "bidirectional"))
      (node (ref "U$44") (pin "P$3") (pinfunction "P$3_P$3") (pintype "bidirectional"))
      (node (ref "U$46") (pin "6") (pinfunction "GND_6") (pintype "bidirectional"))
      (node (ref "U$47") (pin "P$3") (pinfunction "P$3_P$3") (pintype "bidirectional"))
      (node (ref "U$48") (pin "P$3") (pinfunction "P$3_P$3") (pintype "bidirectional"))
      (node (ref "U$50") (pin "6") (pinfunction "GND_6") (pintype "bidirectional"))
      (node (ref "U$51") (pin "P$3") (pinfunction "P$3_P$3") (pintype "bidirectional"))
      (node (ref "U$52") (pin "P$3") (pinfunction "P$3_P$3") (pintype "bidirectional"))
      (node (ref "U$54") (pin "6") (pinfunction "GND_6") (pintype "bidirectional"))
      (node (ref "U$55") (pin "P$3") (pinfunction "P$3_P$3") (pintype "bidirectional"))
      (node (ref "U$56") (pin "P$3") (pinfunction "P$3_P$3") (pintype "bidirectional"))
      (node (ref "U$58") (pin "6") (pinfunction "GND_6") (pintype "bidirectional"))
      (node (ref "U$59") (pin "P$3") (pinfunction "P$3_P$3") (pintype "bidirectional"))
      (node (ref "U$6") (pin "6") (pinfunction "GND_6") (pintype "bidirectional"))
      (node (ref "U$60") (pin "P$3") (pinfunction "P$3_P$3") (pintype "bidirectional"))
      (node (ref "U$62") (pin "6") (pinfunction "GND_6") (pintype "bidirectional"))
      (node (ref "U$63") (pin "P$3") (pinfunction "P$3_P$3") (pintype "bidirectional"))
      (node (ref "U$64") (pin "P$3") (pinfunction "P$3_P$3") (pintype "bidirectional"))
      (node (ref "U$7") (pin "P$3") (pinfunction "P$3_P$3") (pintype "bidirectional"))
      (node (ref "U$8") (pin "P$3") (pinfunction "P$3_P$3") (pintype "bidirectional"))
    )
    (net (code "20") (name "NEG_PAD0") (class "Default")
      (node (ref "U$1") (pin "P$1") (pinfunction "0_P$1") (pintype "bidirectional"))
      (node (ref "U$2") (pin "1") (pinfunction "OUTR_1") (pintype "bidirectional"))
      (node (ref "U$2") (pin "2") (pinfunction "OUTG_2") (pintype "bidirectional"))
      (node (ref "U$2") (pin "3") (pinfunction "OUTB_3") (pintype "bidirectional"))
    )
    (net (code "21") (name "NEG_PAD1") (class "Default")
      (node (ref "U$5") (pin "P$1") (pinfunction "0_P$1") (pintype "bidirectional"))
      (node (ref "U$6") (pin "1") (pinfunction "OUTR_1") (pintype "bidirectional"))
      (node (ref "U$6") (pin "2") (pinfunction "OUTG_2") (pintype "bidirectional"))
      (node (ref "U$6") (pin "3") (pinfunction "OUTB_3") (pintype "bidirectional"))
    )
    (net (code "22") (name "NEG_PAD2") (class "Default")
      (node (ref "U$10") (pin "1") (pinfunction "OUTR_1") (pintype "bidirectional"))
      (node (ref "U$10") (pin "2") (pinfunction "OUTG_2") (pintype "bidirectional"))
      (node (ref "U$10") (pin "3") (pinfunction "OUTB_3") (pintype "bidirectional"))
      (node (ref "U$9") (pin "P$1") (pinfunction "0_P$1") (pintype "bidirectional"))
    )
    (net (code "23") (name "NEG_PAD3") (class "Default")
      (node (ref "U$13") (pin "P$1") (pinfunction "0_P$1") (pintype "bidirectional"))
      (node (ref "U$14") (pin "1") (pinfunction "OUTR_1") (pintype "bidirectional"))
      (node (ref "U$14") (pin "2") (pinfunction "OUTG_2") (pintype "bidirectional"))
      (node (ref "U$14") (pin "3") (pinfunction "OUTB_3") (pintype "bidirectional"))
    )
    (net (code "24") (name "NEG_PAD4") (class "Default")
      (node (ref "U$17") (pin "P$1") (pinfunction "0_P$1") (pintype "bidirectional"))
      (node (ref "U$18") (pin "1") (pinfunction "OUTR_1") (pintype "bidirectional"))
      (node (ref "U$18") (pin "2") (pinfunction "OUTG_2") (pintype "bidirectional"))
      (node (ref "U$18") (pin "3") (pinfunction "OUTB_3") (pintype "bidirectional"))
    )
    (net (code "25") (name "NEG_PAD5") (class "Default")
      (node (ref "U$21") (pin "P$1") (pinfunction "0_P$1") (pintype "bidirectional"))
      (node (ref "U$22") (pin "1") (pinfunction "OUTR_1") (pintype "bidirectional"))
      (node (ref "U$22") (pin "2") (pinfunction "OUTG_2") (pintype "bidirectional"))
      (node (ref "U$22") (pin "3") (pinfunction "OUTB_3") (pintype "bidirectional"))
    )
    (net (code "26") (name "NEG_PAD6") (class "Default")
      (node (ref "U$25") (pin "P$1") (pinfunction "0_P$1") (pintype "bidirectional"))
      (node (ref "U$26") (pin "1") (pinfunction "OUTR_1") (pintype "bidirectional"))
      (node (ref "U$26") (pin "2") (pinfunction "OUTG_2") (pintype "bidirectional"))
      (node (ref "U$26") (pin "3") (pinfunction "OUTB_3") (pintype "bidirectional"))
    )
    (net (code "27") (name "NEG_PAD7") (class "Default")
      (node (ref "U$29") (pin "P$1") (pinfunction "0_P$1") (pintype "bidirectional"))
      (node (ref "U$30") (pin "1") (pinfunction "OUTR_1") (pintype "bidirectional"))
      (node (ref "U$30") (pin "2") (pinfunction "OUTG_2") (pintype "bidirectional"))
      (node (ref "U$30") (pin "3") (pinfunction "OUTB_3") (pintype "bidirectional"))
    )
    (net (code "28") (name "NEG_PAD8") (class "Default")
      (node (ref "U$33") (pin "P$1") (pinfunction "0_P$1") (pintype "bidirectional"))
      (node (ref "U$34") (pin "1") (pinfunction "OUTR_1") (pintype "bidirectional"))
      (node (ref "U$34") (pin "2") (pinfunction "OUTG_2") (pintype "bidirectional"))
      (node (ref "U$34") (pin "3") (pinfunction "OUTB_3") (pintype "bidirectional"))
    )
    (net (code "29") (name "NEG_PAD9") (class "Default")
      (node (ref "U$37") (pin "P$1") (pinfunction "0_P$1") (pintype "bidirectional"))
      (node (ref "U$38") (pin "1") (pinfunction "OUTR_1") (pintype "bidirectional"))
      (node (ref "U$38") (pin "2") (pinfunction "OUTG_2") (pintype "bidirectional"))
      (node (ref "U$38") (pin "3") (pinfunction "OUTB_3") (pintype "bidirectional"))
    )
    (net (code "30") (name "NEG_PAD10") (class "Default")
      (node (ref "U$41") (pin "P$1") (pinfunction "0_P$1") (pintype "bidirectional"))
      (node (ref "U$42") (pin "1") (pinfunction "OUTR_1") (pintype "bidirectional"))
      (node (ref "U$42") (pin "2") (pinfunction "OUTG_2") (pintype "bidirectional"))
      (node (ref "U$42") (pin "3") (pinfunction "OUTB_3") (pintype "bidirectional"))
    )
    (net (code "31") (name "NEG_PAD11") (class "Default")
      (node (ref "U$45") (pin "P$1") (pinfunction "0_P$1") (pintype "bidirectional"))
      (node (ref "U$46") (pin "1") (pinfunction "OUTR_1") (pintype "bidirectional"))
      (node (ref "U$46") (pin "2") (pinfunction "OUTG_2") (pintype "bidirectional"))
      (node (ref "U$46") (pin "3") (pinfunction "OUTB_3") (pintype "bidirectional"))
    )
    (net (code "32") (name "NEG_PAD12") (class "Default")
      (node (ref "U$49") (pin "P$1") (pinfunction "0_P$1") (pintype "bidirectional"))
      (node (ref "U$50") (pin "1") (pinfunction "OUTR_1") (pintype "bidirectional"))
      (node (ref "U$50") (pin "2") (pinfunction "OUTG_2") (pintype "bidirectional"))
      (node (ref "U$50") (pin "3") (pinfunction "OUTB_3") (pintype "bidirectional"))
    )
    (net (code "33") (name "NEG_PAD13") (class "Default")
      (node (ref "U$53") (pin "P$1") (pinfunction "0_P$1") (pintype "bidirectional"))
      (node (ref "U$54") (pin "1") (pinfunction "OUTR_1") (pintype "bidirectional"))
      (node (ref "U$54") (pin "2") (pinfunction "OUTG_2") (pintype "bidirectional"))
      (node (ref "U$54") (pin "3") (pinfunction "OUTB_3") (pintype "bidirectional"))
    )
    (net (code "34") (name "NEG_PAD14") (class "Default")
      (node (ref "U$57") (pin "P$1") (pinfunction "0_P$1") (pintype "bidirectional"))
      (node (ref "U$58") (pin "1") (pinfunction "OUTR_1") (pintype "bidirectional"))
      (node (ref "U$58") (pin "2") (pinfunction "OUTG_2") (pintype "bidirectional"))
      (node (ref "U$58") (pin "3") (pinfunction "OUTB_3") (pintype "bidirectional"))
    )
    (net (code "35") (name "NEG_PAD15") (class "Default")
      (node (ref "U$61") (pin "P$1") (pinfunction "0_P$1") (pintype "bidirectional"))
      (node (ref "U$62") (pin "1") (pinfunction "OUTR_1") (pintype "bidirectional"))
      (node (ref "U$62") (pin "2") (pinfunction "OUTG_2") (pintype "bidirectional"))
      (node (ref "U$62") (pin "3") (pinfunction "OUTB_3") (pintype "bidirectional"))
    )
    (net (code "36") (name "Net-(U$2-DIN)") (class "Default")
      (node (ref "R4") (pin "1") (pinfunction "1_1") (pintype "passive"))
      (node (ref "U$2") (pin "5") (pinfunction "DIN_5") (pintype "bidirectional"))
    )
    (net (code "37") (name "Net-(U$2-DO)") (class "Default")
      (node (ref "R5") (pin "2") (pinfunction "2_2") (pintype "passive"))
      (node (ref "U$2") (pin "4") (pinfunction "DO_4") (pintype "bidirectional"))
    )
    (net (code "38") (name "Net-(U$2-VDD)") (class "Default")
      (node (ref "R6") (pin "1") (pinfunction "1_1") (pintype "passive"))
      (node (ref "U$2") (pin "8") (pinfunction "VDD_8") (pintype "bidirectional"))
    )
    (net (code "39") (name "Net-(U$6-DIN)") (class "Default")
      (node (ref "R1") (pin "1") (pinfunction "1_1") (pintype "passive"))
      (node (ref "U$6") (pin "5") (pinfunction "DIN_5") (pintype "bidirectional"))
    )
    (net (code "40") (name "Net-(U$6-DO)") (class "Default")
      (node (ref "R2") (pin "2") (pinfunction "2_2") (pintype "passive"))
      (node (ref "U$6") (pin "4") (pinfunction "DO_4") (pintype "bidirectional"))
    )
    (net (code "41") (name "Net-(U$6-VDD)") (class "Default")
      (node (ref "R3") (pin "1") (pinfunction "1_1") (pintype "passive"))
      (node (ref "U$6") (pin "8") (pinfunction "VDD_8") (pintype "bidirectional"))
    )
    (net (code "42") (name "Net-(U$10-DIN)") (class "Default")
      (node (ref "R7") (pin "1") (pinfunction "1_1") (pintype "passive"))
      (node (ref "U$10") (pin "5") (pinfunction "DIN_5") (pintype "bidirectional"))
    )
    (net (code "43") (name "Net-(U$10-DO)") (class "Default")
      (node (ref "R8") (pin "2") (pinfunction "2_2") (pintype "passive"))
      (node (ref "U$10") (pin "4") (pinfunction "DO_4") (pintype "bidirectional"))
    )
    (net (code "44") (name "Net-(U$10-VDD)") (class "Default")
      (node (ref "R9") (pin "1") (pinfunction "1_1") (pintype "passive"))
      (node (ref "U$10") (pin "8") (pinfunction "VDD_8") (pintype "bidirectional"))
    )
    (net (code "45") (name "Net-(U$14-DIN)") (class "Default")
      (node (ref "R10") (pin "1") (pinfunction "1_1") (pintype "passive"))
      (node (ref "U$14") (pin "5") (pinfunction "DIN_5") (pintype "bidirectional"))
    )
    (net (code "46") (name "Net-(U$14-DO)") (class "Default")
      (node (ref "R11") (pin "2") (pinfunction "2_2") (pintype "passive"))
      (node (ref "U$14") (pin "4") (pinfunction "DO_4") (pintype "bidirectional"))
    )
    (net (code "47") (name "Net-(U$14-VDD)") (class "Default")
      (node (ref "R12") (pin "1") (pinfunction "1_1") (pintype "passive"))
      (node (ref "U$14") (pin "8") (pinfunction "VDD_8") (pintype "bidirectional"))
    )
    (net (code "48") (name "Net-(U$18-DIN)") (class "Default")
      (node (ref "R13") (pin "1") (pinfunction "1_1") (pintype "passive"))
      (node (ref "U$18") (pin "5") (pinfunction "DIN_5") (pintype "bidirectional"))
    )
    (net (code "49") (name "Net-(U$18-DO)") (class "Default")
      (node (ref "R14") (pin "2") (pinfunction "2_2") (pintype "passive"))
      (node (ref "U$18") (pin "4") (pinfunction "DO_4") (pintype "bidirectional"))
    )
    (net (code "50") (name "Net-(U$18-VDD)") (class "Default")
      (node (ref "R15") (pin "1") (pinfunction "1_1") (pintype "passive"))
      (node (ref "U$18") (pin "8") (pinfunction "VDD_8") (pintype "bidirectional"))
    )
    (net (code "51") (name "Net-(U$22-DIN)") (class "Default")
      (node (ref "R16") (pin "1") (pinfunction "1_1") (pintype "passive"))
      (node (ref "U$22") (pin "5") (pinfunction "DIN_5") (pintype "bidirectional"))
    )
    (net (code "52") (name "Net-(U$22-DO)") (class "Default")
      (node (ref "R17") (pin "2") (pinfunction "2_2") (pintype "passive"))
      (node (ref "U$22") (pin "4") (pinfunction "DO_4") (pintype "bidirectional"))
    )
    (net (code "53") (name "Net-(U$22-VDD)") (class "Default")
      (node (ref "R18") (pin "1") (pinfunction "1_1") (pintype "passive"))
      (node (ref "U$22") (pin "8") (pinfunction "VDD_8") (pintype "bidirectional"))
    )
    (net (code "54") (name "Net-(U$26-DIN)") (class "Default")
      (node (ref "R19") (pin "1") (pinfunction "1_1") (pintype "passive"))
      (node (ref "U$26") (pin "5") (pinfunction "DIN_5") (pintype "bidirectional"))
    )
    (net (code "55") (name "Net-(U$26-DO)") (class "Default")
      (node (ref "R20") (pin "2") (pinfunction "2_2") (pintype "passive"))
      (node (ref "U$26") (pin "4") (pinfunction "DO_4") (pintype "bidirectional"))
    )
    (net (code "56") (name "Net-(U$26-VDD)") (class "Default")
      (node (ref "R21") (pin "1") (pinfunction "1_1") (pintype "passive"))
      (node (ref "U$26") (pin "8") (pinfunction "VDD_8") (pintype "bidirectional"))
    )
    (net (code "57") (name "Net-(U$30-DIN)") (class "Default")
      (node (ref "R22") (pin "1") (pinfunction "1_1") (pintype "passive"))
      (node (ref "U$30") (pin "5") (pinfunction "DIN_5") (pintype "bidirectional"))
    )
    (net (code "58") (name "Net-(U$30-DO)") (class "Default")
      (node (ref "R23") (pin "2") (pinfunction "2_2") (pintype "passive"))
      (node (ref "U$30") (pin "4") (pinfunction "DO_4") (pintype "bidirectional"))
    )
    (net (code "59") (name "Net-(U$30-VDD)") (class "Default")
      (node (ref "R24") (pin "1") (pinfunction "1_1") (pintype "passive"))
      (node (ref "U$30") (pin "8") (pinfunction "VDD_8") (pintype "bidirectional"))
    )
    (net (code "60") (name "Net-(U$34-DIN)") (class "Default")
      (node (ref "R25") (pin "1") (pinfunction "1_1") (pintype "passive"))
      (node (ref "U$34") (pin "5") (pinfunction "DIN_5") (pintype "bidirectional"))
    )
    (net (code "61") (name "Net-(U$34-DO)") (class "Default")
      (node (ref "R26") (pin "2") (pinfunction "2_2") (pintype "passive"))
      (node (ref "U$34") (pin "4") (pinfunction "DO_4") (pintype "bidirectional"))
    )
    (net (code "62") (name "Net-(U$34-VDD)") (class "Default")
      (node (ref "R27") (pin "1") (pinfunction "1_1") (pintype "passive"))
      (node (ref "U$34") (pin "8") (pinfunction "VDD_8") (pintype "bidirectional"))
    )
    (net (code "63") (name "Net-(U$38-DIN)") (class "Default")
      (node (ref "R28") (pin "1") (pinfunction "1_1") (pintype "passive"))
      (node (ref "U$38") (pin "5") (pinfunction "DIN_5") (pintype "bidirectional"))
    )
    (net (code "64") (name "Net-(U$38-DO)") (class "Default")
      (node (ref "R29") (pin "2") (pinfunction "2_2") (pintype "passive"))
      (node (ref "U$38") (pin "4") (pinfunction "DO_4") (pintype "bidirectional"))
    )
    (net (code "65") (name "Net-(U$38-VDD)") (class "Default")
      (node (ref "R30") (pin "1") (pinfunction "1_1") (pintype "passive"))
      (node (ref "U$38") (pin "8") (pinfunction "VDD_8") (pintype "bidirectional"))
    )
    (net (code "66") (name "Net-(U$42-DIN)") (class "Default")
      (node (ref "R31") (pin "1") (pinfunction "1_1") (pintype "passive"))
      (node (ref "U$42") (pin "5") (pinfunction "DIN_5") (pintype "bidirectional"))
    )
    (net (code "67") (name "Net-(U$42-DO)") (class "Default")
      (node (ref "R32") (pin "2") (pinfunction "2_2") (pintype "passive"))
      (node (ref "U$42") (pin "4") (pinfunction "DO_4") (pintype "bidirectional"))
    )
    (net (code "68") (name "Net-(U$42-VDD)") (class "Default")
      (node (ref "R33") (pin "1") (pinfunction "1_1") (pintype "passive"))
      (node (ref "U$42") (pin "8") (pinfunction "VDD_8") (pintype "bidirectional"))
    )
    (net (code "69") (name "Net-(U$46-DIN)") (class "Default")
      (node (ref "R34") (pin "1") (pinfunction "1_1") (pintype "passive"))
      (node (ref "U$46") (pin "5") (pinfunction "DIN_5") (pintype "bidirectional"))
    )
    (net (code "70") (name "Net-(U$46-DO)") (class "Default")
      (node (ref "R35") (pin "2") (pinfunction "2_2") (pintype "passive"))
      (node (ref "U$46") (pin "4") (pinfunction "DO_4") (pintype "bidirectional"))
    )
    (net (code "71") (name "Net-(U$46-VDD)") (class "Default")
      (node (ref "R36") (pin "1") (pinfunction "1_1") (pintype "passive"))
      (node (ref "U$46") (pin "8") (pinfunction "VDD_8") (pintype "bidirectional"))
    )
    (net (code "72") (name "Net-(U$50-DIN)") (class "Default")
      (node (ref "R37") (pin "1") (pinfunction "1_1") (pintype "passive"))
      (node (ref "U$50") (pin "5") (pinfunction "DIN_5") (pintype "bidirectional"))
    )
    (net (code "73") (name "Net-(U$50-DO)") (class "Default")
      (node (ref "R38") (pin "2") (pinfunction "2_2") (pintype "passive"))
      (node (ref "U$50") (pin "4") (pinfunction "DO_4") (pintype "bidirectional"))
    )
    (net (code "74") (name "Net-(U$50-VDD)") (class "Default")
      (node (ref "R39") (pin "1") (pinfunction "1_1") (pintype "passive"))
      (node (ref "U$50") (pin "8") (pinfunction "VDD_8") (pintype "bidirectional"))
    )
    (net (code "75") (name "Net-(U$54-DIN)") (class "Default")
      (node (ref "R40") (pin "1") (pinfunction "1_1") (pintype "passive"))
      (node (ref "U$54") (pin "5") (pinfunction "DIN_5") (pintype "bidirectional"))
    )
    (net (code "76") (name "Net-(U$54-DO)") (class "Default")
      (node (ref "R41") (pin "2") (pinfunction "2_2") (pintype "passive"))
      (node (ref "U$54") (pin "4") (pinfunction "DO_4") (pintype "bidirectional"))
    )
    (net (code "77") (name "Net-(U$54-VDD)") (class "Default")
      (node (ref "R42") (pin "1") (pinfunction "1_1") (pintype "passive"))
      (node (ref "U$54") (pin "8") (pinfunction "VDD_8") (pintype "bidirectional"))
    )
    (net (code "78") (name "Net-(U$58-DIN)") (class "Default")
      (node (ref "R43") (pin "1") (pinfunction "1_1") (pintype "passive"))
      (node (ref "U$58") (pin "5") (pinfunction "DIN_5") (pintype "bidirectional"))
    )
    (net (code "79") (name "Net-(U$58-DO)") (class "Default")
      (node (ref "R44") (pin "2") (pinfunction "2_2") (pintype "passive"))
      (node (ref "U$58") (pin "4") (pinfunction "DO_4") (pintype "bidirectional"))
    )
    (net (code "80") (name "Net-(U$58-VDD)") (class "Default")
      (node (ref "R45") (pin "1") (pinfunction "1_1") (pintype "passive"))
      (node (ref "U$58") (pin "8") (pinfunction "VDD_8") (pintype "bidirectional"))
    )
    (net (code "81") (name "Net-(U$62-DIN)") (class "Default")
      (node (ref "R46") (pin "1") (pinfunction "1_1") (pintype "passive"))
      (node (ref "U$62") (pin "5") (pinfunction "DIN_5") (pintype "bidirectional"))
    )
    (net (code "82") (name "Net-(U$62-DO)") (class "Default")
      (node (ref "R47") (pin "2") (pinfunction "2_2") (pintype "passive"))
      (node (ref "U$62") (pin "4") (pinfunction "DO_4") (pintype "bidirectional"))
    )
    (net (code "83") (name "Net-(U$62-VDD)") (class "Default")
      (node (ref "R48") (pin "1") (pinfunction "1_1") (pintype "passive"))
      (node (ref "U$62") (pin "8") (pinfunction "VDD_8") (pintype "bidirectional"))
    )
    (net (code "84") (name "VCC") (class "Default")
      (node (ref "C1") (pin "1") (pinfunction "1_1") (pintype "passive"))
      (node (ref "C10") (pin "1") (pinfunction "1_1") (pintype "passive"))
      (node (ref "C11") (pin "1") (pinfunction "1_1") (pintype "passive"))
      (node (ref "C12") (pin "1") (pinfunction "1_1") (pintype "passive"))
      (node (ref "C13") (pin "1") (pinfunction "1_1") (pintype "passive"))
      (node (ref "C14") (pin "1") (pinfunction "1_1") (pintype "passive"))
      (node (ref "C15") (pin "1") (pinfunction "1_1") (pintype "passive"))
      (node (ref "C16") (pin "1") (pinfunction "1_1") (pintype "passive"))
      (node (ref "C2") (pin "1") (pinfunction "1_1") (pintype "passive"))
      (node (ref "C3") (pin "1") (pinfunction "1_1") (pintype "passive"))
      (node (ref "C4") (pin "1") (pinfunction "1_1") (pintype "passive"))
      (node (ref "C5") (pin "1") (pinfunction "1_1") (pintype "passive"))
      (node (ref "C6") (pin "1") (pinfunction "1_1") (pintype "passive"))
      (node (ref "C7") (pin "1") (pinfunction "1_1") (pintype "passive"))
      (node (ref "C8") (pin "1") (pinfunction "1_1") (pintype "passive"))
      (node (ref "C9") (pin "1") (pinfunction "1_1") (pintype "passive"))
      (node (ref "R12") (pin "2") (pinfunction "2_2") (pintype "passive"))
      (node (ref "R15") (pin "2") (pinfunction "2_2") (pintype "passive"))
      (node (ref "R18") (pin "2") (pinfunction "2_2") (pintype "passive"))
      (node (ref "R21") (pin "2") (pinfunction "2_2") (pintype "passive"))
      (node (ref "R24") (pin "2") (pinfunction "2_2") (pintype "passive"))
      (node (ref "R27") (pin "2") (pinfunction "2_2") (pintype "passive"))
      (node (ref "R3") (pin "2") (pinfunction "2_2") (pintype "passive"))
      (node (ref "R30") (pin "2") (pinfunction "2_2") (pintype "passive"))
      (node (ref "R33") (pin "2") (pinfunction "2_2") (pintype "passive"))
      (node (ref "R36") (pin "2") (pinfunction "2_2") (pintype "passive"))
      (node (ref "R39") (pin "2") (pinfunction "2_2") (pintype "passive"))
      (node (ref "R42") (pin "2") (pinfunction "2_2") (pintype "passive"))
      (node (ref "R45") (pin "2") (pinfunction "2_2") (pintype "passive"))
      (node (ref "R48") (pin "2") (pinfunction "2_2") (pintype "passive"))
      (node (ref "R6") (pin "2") (pinfunction "2_2") (pintype "passive"))
      (node (ref "R9") (pin "2") (pinfunction "2_2") (pintype "passive"))
      (node (ref "U$1") (pin "P$2") (pinfunction "1_P$2") (pintype "bidirectional"))
      (node (ref "U$11") (pin "P$4") (pinfunction "P$4_P$4") (pintype "bidirectional"))
      (node (ref "U$12") (pin "P$4") (pinfunction "P$4_P$4") (pintype "bidirectional"))
      (node (ref "U$13") (pin "P$2") (pinfunction "1_P$2") (pintype "bidirectional"))
      (node (ref "U$15") (pin "P$4") (pinfunction "P$4_P$4") (pintype "bidirectional"))
      (node (ref "U$16") (pin "P$4") (pinfunction "P$4_P$4") (pintype "bidirectional"))
      (node (ref "U$17") (pin "P$2") (pinfunction "1_P$2") (pintype "bidirectional"))
      (node (ref "U$19") (pin "P$4") (pinfunction "P$4_P$4") (pintype "bidirectional"))
      (node (ref "U$20") (pin "P$4") (pinfunction "P$4_P$4") (pintype "bidirectional"))
      (node (ref "U$21") (pin "P$2") (pinfunction "1_P$2") (pintype "bidirectional"))
      (node (ref "U$23") (pin "P$4") (pinfunction "P$4_P$4") (pintype "bidirectional"))
      (node (ref "U$24") (pin "P$4") (pinfunction "P$4_P$4") (pintype "bidirectional"))
      (node (ref "U$25") (pin "P$2") (pinfunction "1_P$2") (pintype "bidirectional"))
      (node (ref "U$27") (pin "P$4") (pinfunction "P$4_P$4") (pintype "bidirectional"))
      (node (ref "U$28") (pin "P$4") (pinfunction "P$4_P$4") (pintype "bidirectional"))
      (node (ref "U$29") (pin "P$2") (pinfunction "1_P$2") (pintype "bidirectional"))
      (node (ref "U$3") (pin "P$4") (pinfunction "P$4_P$4") (pintype "bidirectional"))
      (node (ref "U$31") (pin "P$4") (pinfunction "P$4_P$4") (pintype "bidirectional"))
      (node (ref "U$32") (pin "P$4") (pinfunction "P$4_P$4") (pintype "bidirectional"))
      (node (ref "U$33") (pin "P$2") (pinfunction "1_P$2") (pintype "bidirectional"))
      (node (ref "U$35") (pin "P$4") (pinfunction "P$4_P$4") (pintype "bidirectional"))
      (node (ref "U$36") (pin "P$4") (pinfunction "P$4_P$4") (pintype "bidirectional"))
      (node (ref "U$37") (pin "P$2") (pinfunction "1_P$2") (pintype "bidirectional"))
      (node (ref "U$39") (pin "P$4") (pinfunction "P$4_P$4") (pintype "bidirectional"))
      (node (ref "U$4") (pin "P$4") (pinfunction "P$4_P$4") (pintype "bidirectional"))
      (node (ref "U$40") (pin "P$4") (pinfunction "P$4_P$4") (pintype "bidirectional"))
      (node (ref "U$41") (pin "P$2") (pinfunction "1_P$2") (pintype "bidirectional"))
      (node (ref "U$43") (pin "P$4") (pinfunction "P$4_P$4") (pintype "bidirectional"))
      (node (ref "U$44") (pin "P$4") (pinfunction "P$4_P$4") (pintype "bidirectional"))
      (node (ref "U$45") (pin "P$2") (pinfunction "1_P$2") (pintype "bidirectional"))
      (node (ref "U$47") (pin "P$4") (pinfunction "P$4_P$4") (pintype "bidirectional"))
      (node (ref "U$48") (pin "P$4") (pinfunction "P$4_P$4") (pintype "bidirectional"))
      (node (ref "U$49") (pin "P$2") (pinfunction "1_P$2") (pintype "bidirectional"))
      (node (ref "U$5") (pin "P$2") (pinfunction "1_P$2") (pintype "bidirectional"))
      (node (ref "U$51") (pin "P$4") (pinfunction "P$4_P$4") (pintype "bidirectional"))
      (node (ref "U$52") (pin "P$4") (pinfunction "P$4_P$4") (pintype "bidirectional"))
      (node (ref "U$53") (pin "P$2") (pinfunction "1_P$2") (pintype "bidirectional"))
      (node (ref "U$55") (pin "P$4") (pinfunction "P$4_P$4") (pintype "bidirectional"))
      (node (ref "U$56") (pin "P$4") (pinfunction "P$4_P$4") (pintype "bidirectional"))
      (node (ref "U$57") (pin "P$2") (pinfunction "1_P$2") (pintype "bidirectional"))
      (node (ref "U$59") (pin "P$4") (pinfunction "P$4_P$4") (pintype "bidirectional"))
      (node (ref "U$60") (pin "P$4") (pinfunction "P$4_P$4") (pintype "bidirectional"))
      (node (ref "U$61") (pin "P$2") (pinfunction "1_P$2") (pintype "bidirectional"))
      (node (ref "U$63") (pin "P$4") (pinfunction "P$4_P$4") (pintype "bidirectional"))
      (node (ref "U$64") (pin "P$4") (pinfunction "P$4_P$4") (pintype "bidirectional"))
      (node (ref "U$7") (pin "P$4") (pinfunction "P$4_P$4") (pintype "bidirectional"))
      (node (ref "U$8") (pin "P$4") (pinfunction "P$4_P$4") (pintype "bidirectional"))
      (node (ref "U$9") (pin "P$2") (pinfunction "1_P$2") (pintype "bidirectional"))
    )
  )
)
